# cd4007.net
KiCad netlist of a schematic drawn in EAGLE
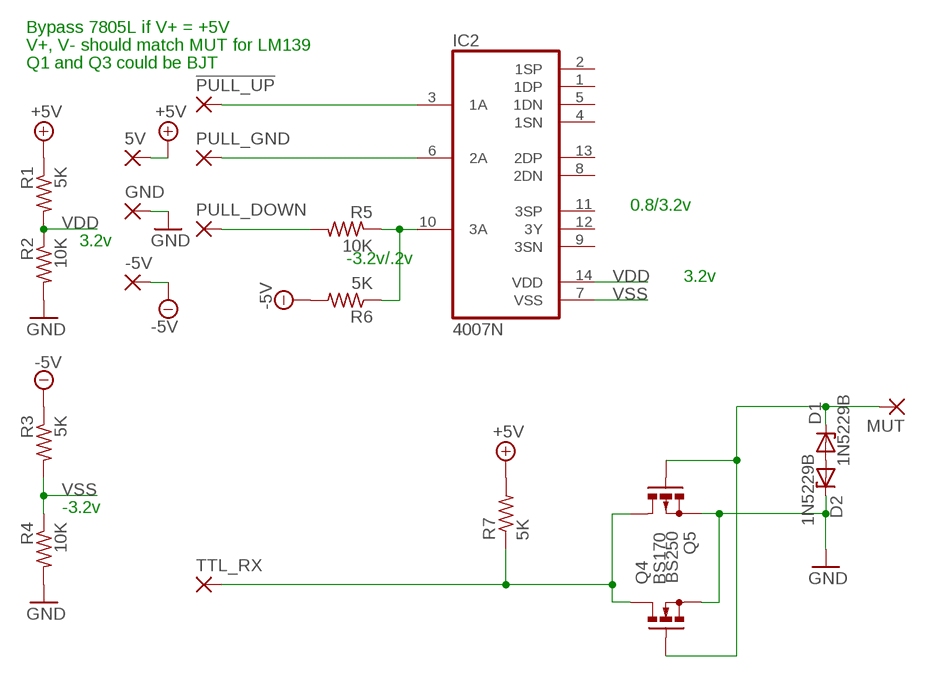
[diagram p0: schematic, sheet 1]

(export (version "E")
  (design (tool "Eeschema 10.0.6"))
  (components
    (comp (ref "!PULL_UP")
      (value "1,6/0,9")
      (footprint "eagle-import:1,6_0,9")
      (libsource (lib "eagle-import") (part "1,6/0,9"))
    )
    (comp (ref "-5V")
      (value "1,6/0,9")
      (footprint "eagle-import:1,6_0,9")
      (libsource (lib "eagle-import") (part "1,6/0,9"))
    )
    (comp (ref "5V")
      (value "1,6/0,9")
      (footprint "eagle-import:1,6_0,9")
      (libsource (lib "eagle-import") (part "1,6/0,9"))
    )
    (comp (ref "D1")
      (value "1N5229B")
      (footprint "eagle-import:DO35Z10")
      (libsource (lib "eagle-import") (part "ZENER-DIODEDO35Z10"))
    )
    (comp (ref "D2")
      (value "1N5229B")
      (footprint "eagle-import:DO35Z10")
      (libsource (lib "eagle-import") (part "ZENER-DIODEDO35Z10"))
    )
    (comp (ref "GND")
      (value "1,6/0,9")
      (footprint "eagle-import:1,6_0,9")
      (libsource (lib "eagle-import") (part "1,6/0,9"))
    )
    (comp (ref "IC2")
      (value "4007N")
      (footprint "eagle-import:DIL14")
      (libsource (lib "eagle-import") (part "4007N"))
    )
    (comp (ref "MUT")
      (value "1,6/0,9")
      (footprint "eagle-import:1,6_0,9")
      (libsource (lib "eagle-import") (part "1,6/0,9"))
    )
    (comp (ref "PULL_DOWN")
      (value "1,6/0,9")
      (footprint "eagle-import:1,6_0,9")
      (libsource (lib "eagle-import") (part "1,6/0,9"))
    )
    (comp (ref "PULL_GND")
      (value "1,6/0,9")
      (footprint "eagle-import:1,6_0,9")
      (libsource (lib "eagle-import") (part "1,6/0,9"))
    )
    (comp (ref "Q4")
      (value "BS170")
      (footprint "eagle-import:SOT54E")
      (libsource (lib "eagle-import") (part "BS170"))
    )
    (comp (ref "Q5")
      (value "BS250")
      (footprint "eagle-import:SOT54E")
      (libsource (lib "eagle-import") (part "BS250"))
    )
    (comp (ref "R1")
      (value "5K")
      (footprint "eagle-import:0207_10")
      (libsource (lib "eagle-import") (part "R-US_0207/10"))
    )
    (comp (ref "R2")
      (value "10K")
      (footprint "eagle-import:0207_10")
      (libsource (lib "eagle-import") (part "R-US_0207/10"))
    )
    (comp (ref "R3")
      (value "5K")
      (footprint "eagle-import:0207_10")
      (libsource (lib "eagle-import") (part "R-US_0207/10"))
    )
    (comp (ref "R4")
      (value "10K")
      (footprint "eagle-import:0207_10")
      (libsource (lib "eagle-import") (part "R-US_0207/10"))
    )
    (comp (ref "R5")
      (value "10K")
      (footprint "eagle-import:0207_10")
      (libsource (lib "eagle-import") (part "R-US_0207/10"))
    )
    (comp (ref "R6")
      (value "5K")
      (footprint "eagle-import:0207_10")
      (libsource (lib "eagle-import") (part "R-US_0207/10"))
    )
    (comp (ref "R7")
      (value "5K")
      (footprint "eagle-import:0207_10")
      (libsource (lib "eagle-import") (part "R-US_0207/10"))
    )
    (comp (ref "TTL_RX")
      (value "1,6/0,9")
      (footprint "eagle-import:1,6_0,9")
      (libsource (lib "eagle-import") (part "1,6/0,9"))
    )
  )
  (nets
    (net (code "1") (name "+5V") (class "Default")
      (node (ref "5V") (pin "1") (pinfunction "P_1") (pintype "passive"))
      (node (ref "R1") (pin "1") (pinfunction "1_1") (pintype "passive"))
      (node (ref "R7") (pin "2") (pinfunction "2_2") (pintype "passive"))
    )
    (net (code "2") (name "-5V") (class "Default")
      (node (ref "-5V") (pin "1") (pinfunction "P_1") (pintype "passive"))
      (node (ref "R3") (pin "1") (pinfunction "1_1") (pintype "passive"))
      (node (ref "R6") (pin "2") (pinfunction "2_2") (pintype "passive"))
    )
    (net (code "3") (name "/VDD") (class "Default")
      (node (ref "IC2") (pin "14") (pinfunction "VDD_14") (pintype "input"))
      (node (ref "R1") (pin "2") (pinfunction "2_2") (pintype "passive"))
      (node (ref "R2") (pin "1") (pinfunction "1_1") (pintype "passive"))
    )
    (net (code "4") (name "/VSS") (class "Default")
      (node (ref "IC2") (pin "7") (pinfunction "VSS_7") (pintype "input"))
      (node (ref "R3") (pin "2") (pinfunction "2_2") (pintype "passive"))
      (node (ref "R4") (pin "1") (pinfunction "1_1") (pintype "passive"))
    )
    (net (code "5") (name "GND") (class "Default")
      (node (ref "D2") (pin "C") (pinfunction "C_C") (pintype "passive"))
      (node (ref "GND") (pin "1") (pinfunction "P_1") (pintype "passive"))
      (node (ref "Q4") (pin "S") (pinfunction "S_S") (pintype "passive"))
      (node (ref "Q5") (pin "S") (pinfunction "S_S") (pintype "passive"))
      (node (ref "R2") (pin "2") (pinfunction "2_2") (pintype "passive"))
      (node (ref "R4") (pin "2") (pinfunction "2_2") (pintype "passive"))
    )
    (net (code "6") (name "Net-(!PULL_UP-P)") (class "Default")
      (node (ref "!PULL_UP") (pin "1") (pinfunction "P_1") (pintype "passive"))
      (node (ref "IC2") (pin "3") (pinfunction "1A_3") (pintype "input"))
    )
    (net (code "7") (name "Net-(D1-PadA)") (class "Default")
      (node (ref "D1") (pin "A") (pinfunction "A_A") (pintype "passive"))
      (node (ref "D2") (pin "A") (pinfunction "A_A") (pintype "passive"))
    )
    (net (code "8") (name "Net-(IC2-2A)") (class "Default")
      (node (ref "IC2") (pin "6") (pinfunction "2A_6") (pintype "input"))
      (node (ref "PULL_GND") (pin "1") (pinfunction "P_1") (pintype "passive"))
    )
    (net (code "9") (name "Net-(IC2-3A)") (class "Default")
      (node (ref "IC2") (pin "10") (pinfunction "3A_10") (pintype "input"))
      (node (ref "R5") (pin "1") (pinfunction "1_1") (pintype "passive"))
      (node (ref "R6") (pin "1") (pinfunction "1_1") (pintype "passive"))
    )
    (net (code "10") (name "Net-(MUT-P)") (class "Default")
      (node (ref "D1") (pin "C") (pinfunction "C_C") (pintype "passive"))
      (node (ref "MUT") (pin "1") (pinfunction "P_1") (pintype "passive"))
      (node (ref "Q4") (pin "G") (pinfunction "G_G") (pintype "passive"))
      (node (ref "Q5") (pin "G") (pinfunction "G_G") (pintype "passive"))
    )
    (net (code "11") (name "Net-(PULL_DOWN-P)") (class "Default")
      (node (ref "PULL_DOWN") (pin "1") (pinfunction "P_1") (pintype "passive"))
      (node (ref "R5") (pin "2") (pinfunction "2_2") (pintype "passive"))
    )
    (net (code "12") (name "Net-(TTL_RX-P)") (class "Default")
      (node (ref "Q4") (pin "D") (pinfunction "D_D") (pintype "passive"))
      (node (ref "Q5") (pin "D") (pinfunction "D_D") (pintype "passive"))
      (node (ref "R7") (pin "1") (pinfunction "1_1") (pintype "passive"))
      (node (ref "TTL_RX") (pin "1") (pinfunction "P_1") (pintype "passive"))
    )
    (net (code "13") (name "unconnected-(IC2-1DN-Pad5)") (class "Default")
      (node (ref "IC2") (pin "5") (pinfunction "1DN_5") (pintype "open_collector"))
    )
    (net (code "14") (name "unconnected-(IC2-1DP-Pad1)") (class "Default")
      (node (ref "IC2") (pin "1") (pinfunction "1DP_1") (pintype "open_collector"))
    )
    (net (code "15") (name "unconnected-(IC2-1SN-Pad4)") (class "Default")
      (node (ref "IC2") (pin "4") (pinfunction "1SN_4") (pintype "open_collector"))
    )
    (net (code "16") (name "unconnected-(IC2-1SP-Pad2)") (class "Default")
      (node (ref "IC2") (pin "2") (pinfunction "1SP_2") (pintype "open_collector"))
    )
    (net (code "17") (name "unconnected-(IC2-2DN-Pad8)") (class "Default")
      (node (ref "IC2") (pin "8") (pinfunction "2DN_8") (pintype "bidirectional"))
    )
    (net (code "18") (name "unconnected-(IC2-2DP-Pad13)") (class "Default")
      (node (ref "IC2") (pin "13") (pinfunction "2DP_13") (pintype "bidirectional"))
    )
    (net (code "19") (name "unconnected-(IC2-3SN-Pad9)") (class "Default")
      (node (ref "IC2") (pin "9") (pinfunction "3SN_9") (pintype "bidirectional"))
    )
    (net (code "20") (name "unconnected-(IC2-3SP-Pad11)") (class "Default")
      (node (ref "IC2") (pin "11") (pinfunction "3SP_11") (pintype "bidirectional"))
    )
    (net (code "21") (name "unconnected-(IC2-3Y-Pad12)") (class "Default")
      (node (ref "IC2") (pin "12") (pinfunction "3Y_12") (pintype "bidirectional"))
    )
  )
)
